# XOR.net
KiCad netlist of a schematic drawn in EAGLE
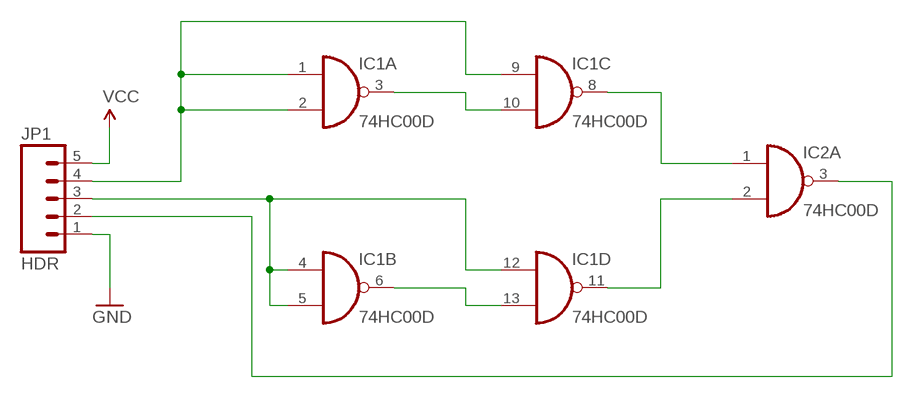
[diagram p0: schematic, sheet 1]

(export (version "E")
  (design (tool "Eeschema 10.0.6"))
  (components
    (comp (ref "IC1")
      (value "74HC00D")
      (footprint "eagle-import:SO14")
      (libsource (lib "eagle-import") (part "7400DHC"))
    )
    (comp (ref "IC2")
      (value "74HC00D")
      (footprint "eagle-import:SO14")
      (libsource (lib "eagle-import") (part "7400DHC"))
    )
    (comp (ref "JP1")
      (value "HDR")
      (footprint "eagle-import:1X05_LOCK")
      (libsource (lib "eagle-import") (part "M05LOCK"))
    )
  )
  (nets
    (net (code "1") (name "GND") (class "Default")
      (node (ref "JP1") (pin "1") (pinfunction "1_1") (pintype "passive"))
    )
    (net (code "2") (name "Net-(IC1A-I0)") (class "Default")
      (node (ref "IC1") (pin "1") (pinfunction "I0_1") (pintype "input"))
      (node (ref "IC1") (pin "2") (pinfunction "I1_2") (pintype "input"))
      (node (ref "IC1") (pin "9") (pinfunction "I0_9") (pintype "input"))
      (node (ref "JP1") (pin "4") (pinfunction "4_4") (pintype "passive"))
    )
    (net (code "3") (name "Net-(IC1A-O)") (class "Default")
      (node (ref "IC1") (pin "10") (pinfunction "I1_10") (pintype "input"))
      (node (ref "IC1") (pin "3") (pinfunction "O_3") (pintype "output"))
    )
    (net (code "4") (name "Net-(IC1B-I0)") (class "Default")
      (node (ref "IC1") (pin "12") (pinfunction "I0_12") (pintype "input"))
      (node (ref "IC1") (pin "4") (pinfunction "I0_4") (pintype "input"))
      (node (ref "IC1") (pin "5") (pinfunction "I1_5") (pintype "input"))
      (node (ref "JP1") (pin "3") (pinfunction "3_3") (pintype "passive"))
    )
    (net (code "5") (name "Net-(IC1B-O)") (class "Default")
      (node (ref "IC1") (pin "13") (pinfunction "I1_13") (pintype "input"))
      (node (ref "IC1") (pin "6") (pinfunction "O_6") (pintype "output"))
    )
    (net (code "6") (name "Net-(IC1C-O)") (class "Default")
      (node (ref "IC1") (pin "8") (pinfunction "O_8") (pintype "output"))
      (node (ref "IC2") (pin "1") (pinfunction "I0_1") (pintype "input"))
    )
    (net (code "7") (name "Net-(IC1D-O)") (class "Default")
      (node (ref "IC1") (pin "11") (pinfunction "O_11") (pintype "output"))
      (node (ref "IC2") (pin "2") (pinfunction "I1_2") (pintype "input"))
    )
    (net (code "8") (name "Net-(IC2A-O)") (class "Default")
      (node (ref "IC2") (pin "3") (pinfunction "O_3") (pintype "output"))
      (node (ref "JP1") (pin "2") (pinfunction "2_2") (pintype "passive"))
    )
    (net (code "9") (name "VCC") (class "Default")
      (node (ref "JP1") (pin "5") (pinfunction "5_5") (pintype "passive"))
    )
  )
)
